# samd11-breakout-for-milling.net
KiCad netlist of a schematic drawn in EAGLE
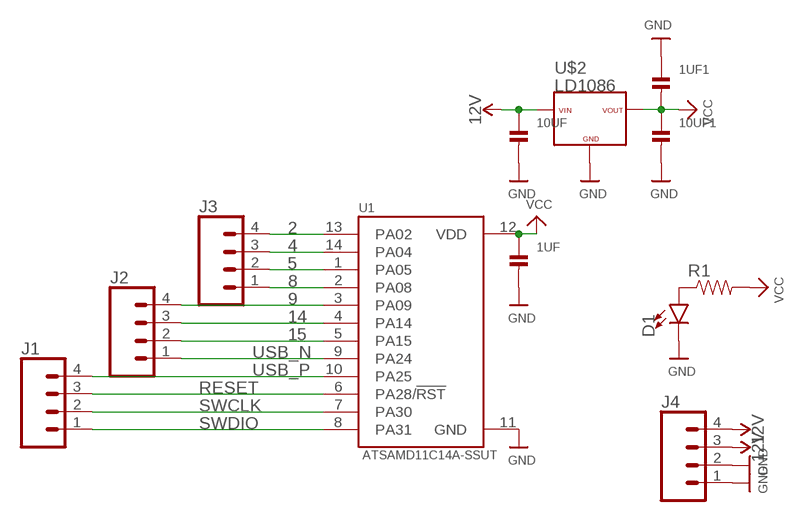
[diagram p0: schematic, sheet 1]

(export (version "E")
  (design (tool "Eeschema 10.0.6"))
  (components
    (comp (ref "1UF")
      (value "CAP_CERAMIC0603")
      (footprint "eagle-import:0603")
      (libsource (lib "eagle-import") (part "CAP_CERAMIC0603"))
    )
    (comp (ref "1UF1")
      (value "CAP_CERAMIC0603")
      (footprint "eagle-import:0603")
      (libsource (lib "eagle-import") (part "CAP_CERAMIC0603"))
    )
    (comp (ref "10UF")
      (value "CAP_CERAMIC0805")
      (footprint "eagle-import:0805")
      (libsource (lib "eagle-import") (part "CAP_CERAMIC0805"))
    )
    (comp (ref "10UF1")
      (value "CAP_CERAMIC0805")
      (footprint "eagle-import:0805")
      (libsource (lib "eagle-import") (part "CAP_CERAMIC0805"))
    )
    (comp (ref "D1")
      (value "LED5MM-KIT")
      (footprint "eagle-import:LED_5MM-KIT")
      (libsource (lib "eagle-import") (part "LED5MM-KIT"))
    )
    (comp (ref "J1")
      (value "CONN_04SMD_RA_FEMALE")
      (footprint "eagle-import:1X04_SMD_RA_FEMALE")
      (libsource (lib "eagle-import") (part "CONN_04SMD_RA_FEMALE"))
    )
    (comp (ref "J2")
      (value "CONN_04SMD_RA_FEMALE")
      (footprint "eagle-import:1X04_SMD_RA_FEMALE")
      (libsource (lib "eagle-import") (part "CONN_04SMD_RA_FEMALE"))
    )
    (comp (ref "J3")
      (value "CONN_04SMD_RA_FEMALE")
      (footprint "eagle-import:1X04_SMD_RA_FEMALE")
      (libsource (lib "eagle-import") (part "CONN_04SMD_RA_FEMALE"))
    )
    (comp (ref "J4")
      (value "CONN_04SMD_RA_FEMALE")
      (footprint "eagle-import:1X04_SMD_RA_FEMALE")
      (libsource (lib "eagle-import") (part "CONN_04SMD_RA_FEMALE"))
    )
    (comp (ref "R1")
      (value "RESISTOR1206")
      (footprint "eagle-import:1206")
      (libsource (lib "eagle-import") (part "RESISTOR1206"))
    )
    (comp (ref "U$2")
      (value "LD1086")
      (footprint "eagle-import:D2PAK")
      (fields (field (name "MF") "STMicroelectronics"))
      (libsource (lib "eagle-import") (part "LD1086"))
    )
    (comp (ref "U1")
      (value "ATSAMD11C14A-SSUT")
      (footprint "eagle-import:SOIC127P600X160-14N")
      (fields (field (name "MF") "Microchip"))
      (libsource (lib "eagle-import") (part "ATSAMD11C14A-SSUT"))
    )
  )
  (nets
    (net (code "1") (name "/2") (class "Default")
      (node (ref "J3") (pin "4") (pinfunction "4_4") (pintype "passive"))
      (node (ref "U1") (pin "13") (pinfunction "PA02_13") (pintype "bidirectional"))
    )
    (net (code "2") (name "/4") (class "Default")
      (node (ref "J3") (pin "3") (pinfunction "3_3") (pintype "passive"))
      (node (ref "U1") (pin "14") (pinfunction "PA04_14") (pintype "bidirectional"))
    )
    (net (code "3") (name "/5") (class "Default")
      (node (ref "J3") (pin "2") (pinfunction "2_2") (pintype "passive"))
      (node (ref "U1") (pin "1") (pinfunction "PA05_1") (pintype "bidirectional"))
    )
    (net (code "4") (name "/8") (class "Default")
      (node (ref "J3") (pin "1") (pinfunction "1_1") (pintype "passive"))
      (node (ref "U1") (pin "2") (pinfunction "PA08_2") (pintype "bidirectional"))
    )
    (net (code "5") (name "/9") (class "Default")
      (node (ref "J2") (pin "4") (pinfunction "4_4") (pintype "passive"))
      (node (ref "U1") (pin "3") (pinfunction "PA09_3") (pintype "bidirectional"))
    )
    (net (code "6") (name "/14") (class "Default")
      (node (ref "J2") (pin "3") (pinfunction "3_3") (pintype "passive"))
      (node (ref "U1") (pin "4") (pinfunction "PA14_4") (pintype "bidirectional"))
    )
    (net (code "7") (name "/15") (class "Default")
      (node (ref "J2") (pin "2") (pinfunction "2_2") (pintype "passive"))
      (node (ref "U1") (pin "5") (pinfunction "PA15_5") (pintype "bidirectional"))
    )
    (net (code "8") (name "/RESET") (class "Default")
      (node (ref "J1") (pin "3") (pinfunction "3_3") (pintype "passive"))
      (node (ref "U1") (pin "6") (pinfunction "PA28/~{RST}_6") (pintype "bidirectional"))
    )
    (net (code "9") (name "/SWCLK") (class "Default")
      (node (ref "J1") (pin "2") (pinfunction "2_2") (pintype "passive"))
      (node (ref "U1") (pin "7") (pinfunction "PA30_7") (pintype "bidirectional"))
    )
    (net (code "10") (name "/SWDIO") (class "Default")
      (node (ref "J1") (pin "1") (pinfunction "1_1") (pintype "passive"))
      (node (ref "U1") (pin "8") (pinfunction "PA31_8") (pintype "bidirectional"))
    )
    (net (code "11") (name "/USB_N") (class "Default")
      (node (ref "J2") (pin "1") (pinfunction "1_1") (pintype "passive"))
      (node (ref "U1") (pin "9") (pinfunction "PA24_9") (pintype "bidirectional"))
    )
    (net (code "12") (name "/USB_P") (class "Default")
      (node (ref "J1") (pin "4") (pinfunction "4_4") (pintype "passive"))
      (node (ref "U1") (pin "10") (pinfunction "PA25_10") (pintype "bidirectional"))
    )
    (net (code "13") (name "12V") (class "Default")
      (node (ref "10UF") (pin "1") (pinfunction "P$1_1") (pintype "passive"))
      (node (ref "J4") (pin "3") (pinfunction "3_3") (pintype "passive"))
      (node (ref "J4") (pin "4") (pinfunction "4_4") (pintype "passive"))
      (node (ref "U$2") (pin "VIN") (pinfunction "VIN_VIN") (pintype "bidirectional"))
    )
    (net (code "14") (name "GND") (class "Default")
      (node (ref "10UF") (pin "2") (pinfunction "P$2_2") (pintype "passive"))
      (node (ref "10UF1") (pin "2") (pinfunction "P$2_2") (pintype "passive"))
      (node (ref "1UF") (pin "2") (pinfunction "P$2_2") (pintype "passive"))
      (node (ref "1UF1") (pin "1") (pinfunction "P$1_1") (pintype "passive"))
      (node (ref "D1") (pin "K") (pinfunction "C_K") (pintype "passive"))
      (node (ref "J4") (pin "1") (pinfunction "1_1") (pintype "passive"))
      (node (ref "J4") (pin "2") (pinfunction "2_2") (pintype "passive"))
      (node (ref "U$2") (pin "GND") (pinfunction "GND_GND") (pintype "bidirectional"))
      (node (ref "U1") (pin "11") (pinfunction "GND_11") (pintype "power_in"))
    )
    (net (code "15") (name "Net-(D1-PadA)") (class "Default")
      (node (ref "D1") (pin "A") (pinfunction "A_A") (pintype "passive"))
      (node (ref "R1") (pin "1") (pinfunction "1_1") (pintype "passive"))
    )
    (net (code "16") (name "VCC") (class "Default")
      (node (ref "10UF1") (pin "1") (pinfunction "P$1_1") (pintype "passive"))
      (node (ref "1UF") (pin "1") (pinfunction "P$1_1") (pintype "passive"))
      (node (ref "1UF1") (pin "2") (pinfunction "P$2_2") (pintype "passive"))
      (node (ref "R1") (pin "2") (pinfunction "2_2") (pintype "passive"))
      (node (ref "U$2") (pin "VOUT") (pinfunction "VOUT_VOUT") (pintype "bidirectional"))
      (node (ref "U1") (pin "12") (pinfunction "VDD_12") (pintype "power_in"))
    )
  )
)
